# ASD2841.net
KiCad netlist of a schematic drawn in EAGLE
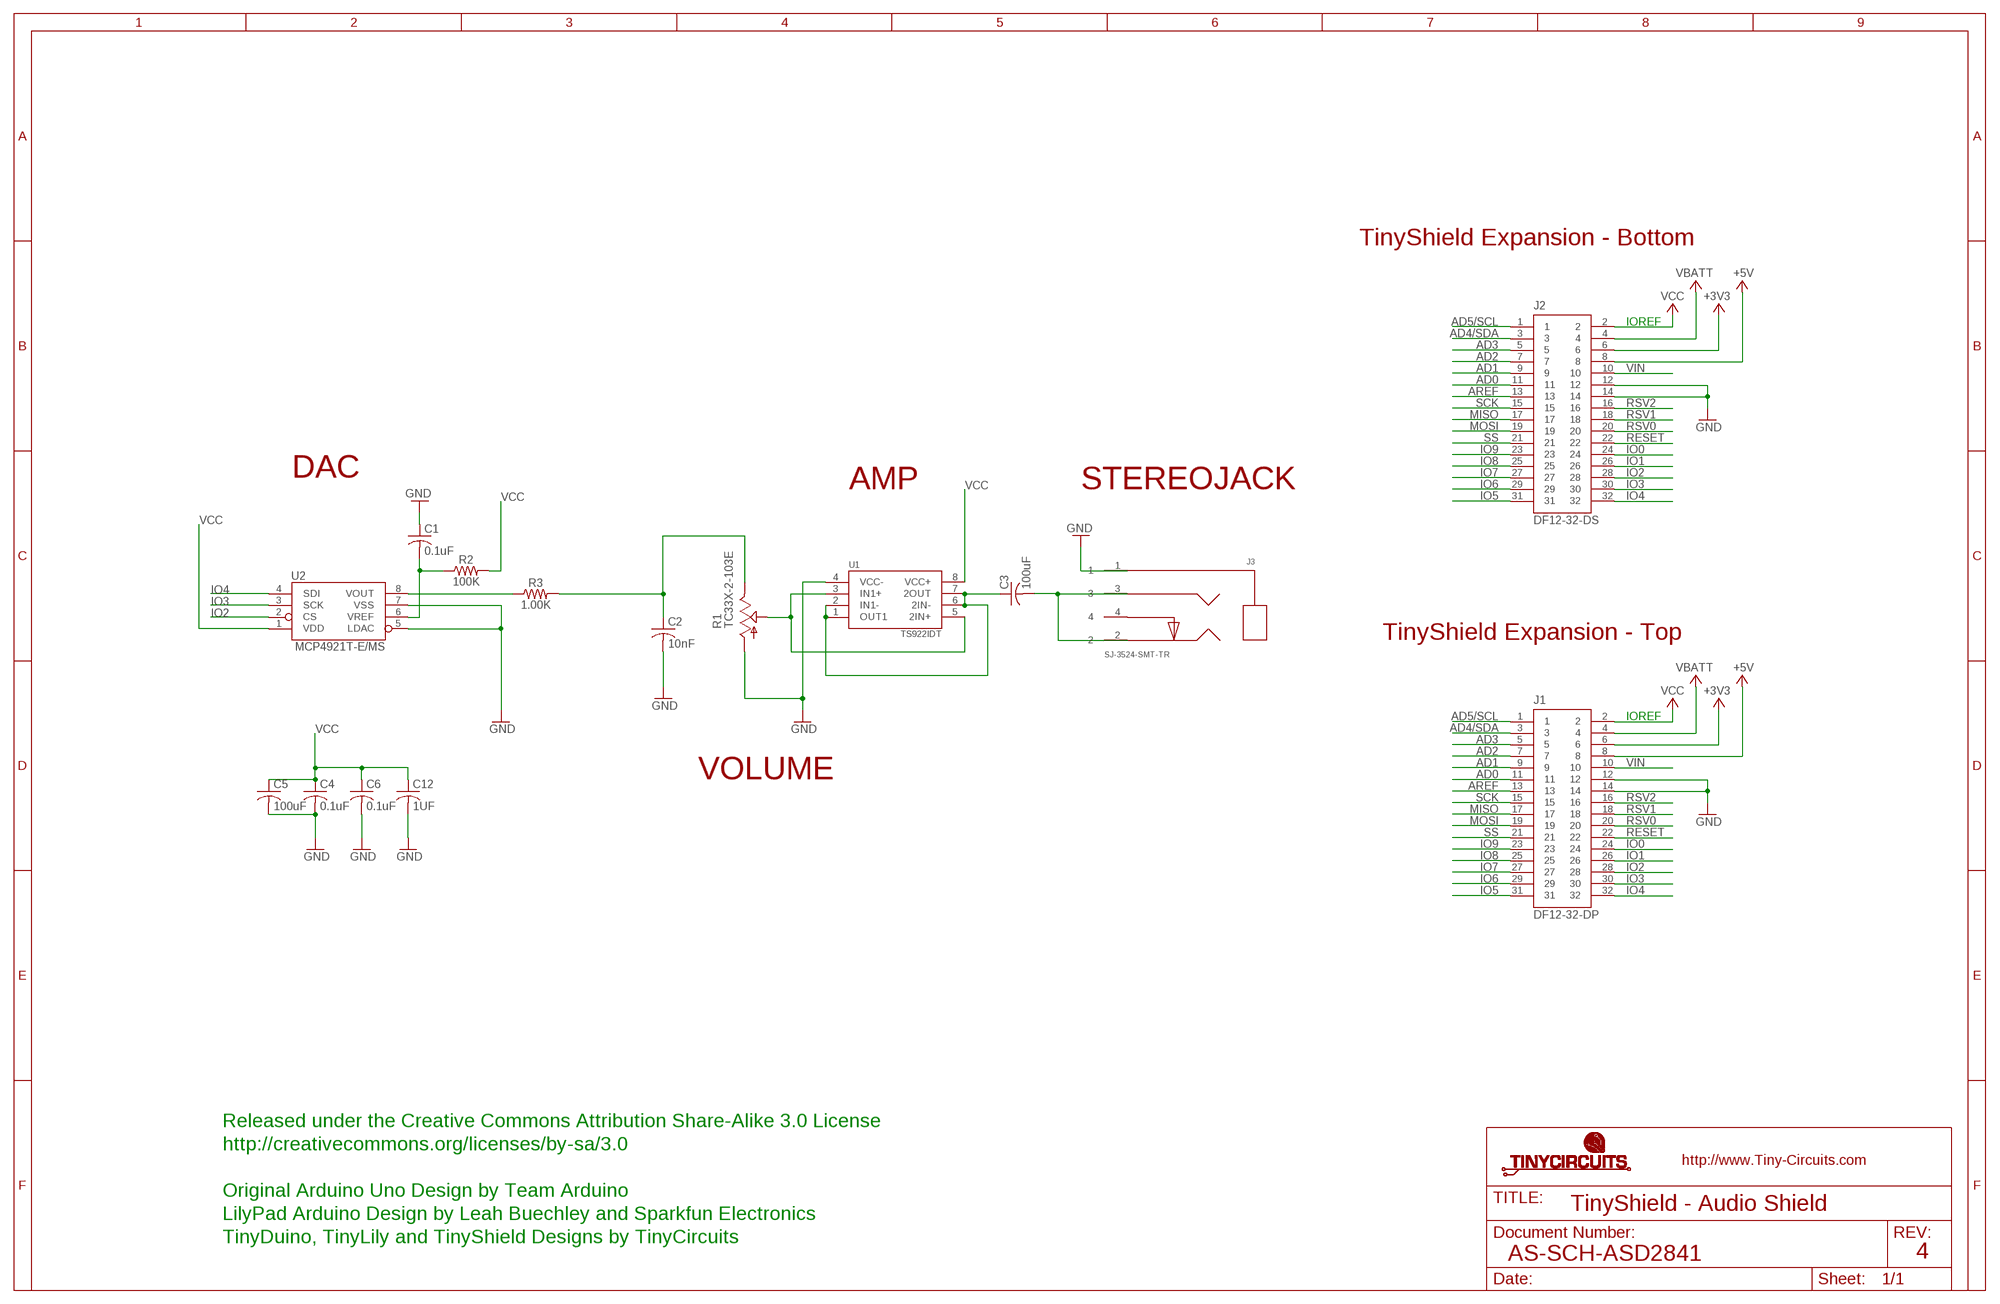
[diagram p0: schematic, sheet 1]

(export (version "E")
  (design (tool "Eeschema 10.0.6"))
  (components
    (comp (ref "C1")
      (value "0.1uF")
      (footprint "eagle-import:C0402")
      (fields (field (name "PARTNO") "AS-ITM-00008"))
      (libsource (lib "eagle-import") (part "AS-ITM-00008"))
    )
    (comp (ref "C2")
      (value "10nF")
      (footprint "eagle-import:C0402")
      (fields (field (name "PARTNO") "AS-ITM-00084"))
      (libsource (lib "eagle-import") (part "AS-ITM-00084"))
    )
    (comp (ref "C3")
      (value "100uF")
      (footprint "eagle-import:C1206")
      (fields (field (name "PARTNO") "AS-ITM-00095"))
      (libsource (lib "eagle-import") (part "AS-ITM-00095"))
    )
    (comp (ref "C4")
      (value "0.1uF")
      (footprint "eagle-import:C0402")
      (fields (field (name "PARTNO") "AS-ITM-00008"))
      (libsource (lib "eagle-import") (part "AS-ITM-00008"))
    )
    (comp (ref "C5")
      (value "100uF")
      (footprint "eagle-import:C1206")
      (fields (field (name "PARTNO") "AS-ITM-00095"))
      (libsource (lib "eagle-import") (part "AS-ITM-00095"))
    )
    (comp (ref "C6")
      (value "0.1uF")
      (footprint "eagle-import:C0402")
      (fields (field (name "PARTNO") "AS-ITM-00008") (field (name "PARTNO_1") "AS-ITM-00008"))
      (libsource (lib "eagle-import") (part "AS-ITM-00008"))
    )
    (comp (ref "C12")
      (value "1UF")
      (footprint "eagle-import:C0402")
      (fields (field (name "PARTNO") "AS-ITM-00105") (field (name "PARTNO_1") "AS-ITM-00105"))
      (libsource (lib "eagle-import") (part "AS-ITM-00105"))
    )
    (comp (ref "J1")
      (value "DF12-32-DP")
      (footprint "eagle-import:DF12-32-DP")
      (fields (field (name "PARTNO") "AS-ITM-00015") (field (name "PARTNO_1") "AS-ITM-00015"))
      (libsource (lib "eagle-import") (part "AS-ITM-00015"))
    )
    (comp (ref "J2")
      (value "DF12-32-DS")
      (footprint "eagle-import:DF12-32-DS")
      (fields (field (name "PARTNO") "AS-ITM-00012") (field (name "PARTNO_1") "AS-ITM-00012"))
      (libsource (lib "eagle-import") (part "AS-ITM-00012"))
    )
    (comp (ref "J3")
      (value "SJ-3524-SMT-TR")
      (footprint "eagle-import:SJ-3524-SMT-TR")
      (fields (field (name "PARTNO") "AS-ITM-00094"))
      (libsource (lib "eagle-import") (part "AS-ITM-00094"))
    )
    (comp (ref "R1")
      (value "TC33X-2-103E")
      (footprint "eagle-import:TC33X-2-104E")
      (fields (field (name "PARTNO") "AS-ITM-00187"))
      (libsource (lib "eagle-import") (part "AS-ITM-00187"))
    )
    (comp (ref "R2")
      (value "100K")
      (footprint "eagle-import:0402")
      (fields (field (name "PARTNO") "AS-ITM-00004"))
      (libsource (lib "eagle-import") (part "AS-ITM-00004"))
    )
    (comp (ref "R3")
      (value "1.00K")
      (footprint "eagle-import:0402")
      (fields (field (name "PARTNO") "AS-ITM-00003"))
      (libsource (lib "eagle-import") (part "AS-ITM-00003"))
    )
    (comp (ref "U1")
      (value "TS922IDT")
      (footprint "eagle-import:SO-08")
      (fields (field (name "PARTNO") "AS-ITM-00092"))
      (libsource (lib "eagle-import") (part "AS-ITM-00092"))
    )
    (comp (ref "U2")
      (value "MCP4921T-E/MS")
      (footprint "eagle-import:MSOP8")
      (fields (field (name "PARTNO") "AS-ITM-00091"))
      (libsource (lib "eagle-import") (part "AS-ITM-00091"))
    )
  )
  (nets
    (net (code "1") (name "+3V3") (class "Default")
      (node (ref "J1") (pin "6") (pinfunction "6_6") (pintype "bidirectional"))
      (node (ref "J2") (pin "6") (pinfunction "6_6") (pintype "bidirectional"))
    )
    (net (code "2") (name "+5V") (class "Default")
      (node (ref "J1") (pin "8") (pinfunction "8_8") (pintype "bidirectional"))
      (node (ref "J2") (pin "8") (pinfunction "8_8") (pintype "bidirectional"))
    )
    (net (code "3") (name "/AD0") (class "Default")
      (node (ref "J1") (pin "11") (pinfunction "11_11") (pintype "bidirectional"))
      (node (ref "J2") (pin "11") (pinfunction "11_11") (pintype "bidirectional"))
    )
    (net (code "4") (name "/AD1") (class "Default")
      (node (ref "J1") (pin "9") (pinfunction "9_9") (pintype "bidirectional"))
      (node (ref "J2") (pin "9") (pinfunction "9_9") (pintype "bidirectional"))
    )
    (net (code "5") (name "/AD2") (class "Default")
      (node (ref "J1") (pin "7") (pinfunction "7_7") (pintype "bidirectional"))
      (node (ref "J2") (pin "7") (pinfunction "7_7") (pintype "bidirectional"))
    )
    (net (code "6") (name "/AD3") (class "Default")
      (node (ref "J1") (pin "5") (pinfunction "5_5") (pintype "bidirectional"))
      (node (ref "J2") (pin "5") (pinfunction "5_5") (pintype "bidirectional"))
    )
    (net (code "7") (name "/AD4{slash}SDA") (class "Default")
      (node (ref "J1") (pin "3") (pinfunction "3_3") (pintype "bidirectional"))
      (node (ref "J2") (pin "3") (pinfunction "3_3") (pintype "bidirectional"))
    )
    (net (code "8") (name "/AD5{slash}SCL") (class "Default")
      (node (ref "J1") (pin "1") (pinfunction "1_1") (pintype "bidirectional"))
      (node (ref "J2") (pin "1") (pinfunction "1_1") (pintype "bidirectional"))
    )
    (net (code "9") (name "/AREF") (class "Default")
      (node (ref "J1") (pin "13") (pinfunction "13_13") (pintype "bidirectional"))
      (node (ref "J2") (pin "13") (pinfunction "13_13") (pintype "bidirectional"))
    )
    (net (code "10") (name "/IO0") (class "Default")
      (node (ref "J1") (pin "24") (pinfunction "24_24") (pintype "bidirectional"))
      (node (ref "J2") (pin "24") (pinfunction "24_24") (pintype "bidirectional"))
    )
    (net (code "11") (name "/IO1") (class "Default")
      (node (ref "J1") (pin "26") (pinfunction "26_26") (pintype "bidirectional"))
      (node (ref "J2") (pin "26") (pinfunction "26_26") (pintype "bidirectional"))
    )
    (net (code "12") (name "/IO2") (class "Default")
      (node (ref "J1") (pin "28") (pinfunction "28_28") (pintype "bidirectional"))
      (node (ref "J2") (pin "28") (pinfunction "28_28") (pintype "bidirectional"))
      (node (ref "U2") (pin "2") (pinfunction "CS_2") (pintype "bidirectional"))
    )
    (net (code "13") (name "/IO3") (class "Default")
      (node (ref "J1") (pin "30") (pinfunction "30_30") (pintype "bidirectional"))
      (node (ref "J2") (pin "30") (pinfunction "30_30") (pintype "bidirectional"))
      (node (ref "U2") (pin "3") (pinfunction "SCK_3") (pintype "bidirectional"))
    )
    (net (code "14") (name "/IO4") (class "Default")
      (node (ref "J1") (pin "32") (pinfunction "32_32") (pintype "bidirectional"))
      (node (ref "J2") (pin "32") (pinfunction "32_32") (pintype "bidirectional"))
      (node (ref "U2") (pin "4") (pinfunction "SDI_4") (pintype "bidirectional"))
    )
    (net (code "15") (name "/IO5") (class "Default")
      (node (ref "J1") (pin "31") (pinfunction "31_31") (pintype "bidirectional"))
      (node (ref "J2") (pin "31") (pinfunction "31_31") (pintype "bidirectional"))
    )
    (net (code "16") (name "/IO6") (class "Default")
      (node (ref "J1") (pin "29") (pinfunction "29_29") (pintype "bidirectional"))
      (node (ref "J2") (pin "29") (pinfunction "29_29") (pintype "bidirectional"))
    )
    (net (code "17") (name "/IO7") (class "Default")
      (node (ref "J1") (pin "27") (pinfunction "27_27") (pintype "bidirectional"))
      (node (ref "J2") (pin "27") (pinfunction "27_27") (pintype "bidirectional"))
    )
    (net (code "18") (name "/IO8") (class "Default")
      (node (ref "J1") (pin "25") (pinfunction "25_25") (pintype "bidirectional"))
      (node (ref "J2") (pin "25") (pinfunction "25_25") (pintype "bidirectional"))
    )
    (net (code "19") (name "/IO9") (class "Default")
      (node (ref "J1") (pin "23") (pinfunction "23_23") (pintype "bidirectional"))
      (node (ref "J2") (pin "23") (pinfunction "23_23") (pintype "bidirectional"))
    )
    (net (code "20") (name "/MISO") (class "Default")
      (node (ref "J1") (pin "17") (pinfunction "17_17") (pintype "bidirectional"))
      (node (ref "J2") (pin "17") (pinfunction "17_17") (pintype "bidirectional"))
    )
    (net (code "21") (name "/MOSI") (class "Default")
      (node (ref "J1") (pin "19") (pinfunction "19_19") (pintype "bidirectional"))
      (node (ref "J2") (pin "19") (pinfunction "19_19") (pintype "bidirectional"))
    )
    (net (code "22") (name "/RESET") (class "Default")
      (node (ref "J1") (pin "22") (pinfunction "22_22") (pintype "bidirectional"))
      (node (ref "J2") (pin "22") (pinfunction "22_22") (pintype "bidirectional"))
    )
    (net (code "23") (name "/RSV0") (class "Default")
      (node (ref "J1") (pin "20") (pinfunction "20_20") (pintype "bidirectional"))
      (node (ref "J2") (pin "20") (pinfunction "20_20") (pintype "bidirectional"))
    )
    (net (code "24") (name "/RSV1") (class "Default")
      (node (ref "J1") (pin "18") (pinfunction "18_18") (pintype "bidirectional"))
      (node (ref "J2") (pin "18") (pinfunction "18_18") (pintype "bidirectional"))
    )
    (net (code "25") (name "/RSV2") (class "Default")
      (node (ref "J1") (pin "16") (pinfunction "16_16") (pintype "bidirectional"))
      (node (ref "J2") (pin "16") (pinfunction "16_16") (pintype "bidirectional"))
    )
    (net (code "26") (name "/SCK") (class "Default")
      (node (ref "J1") (pin "15") (pinfunction "15_15") (pintype "bidirectional"))
      (node (ref "J2") (pin "15") (pinfunction "15_15") (pintype "bidirectional"))
    )
    (net (code "27") (name "/SS") (class "Default")
      (node (ref "J1") (pin "21") (pinfunction "21_21") (pintype "bidirectional"))
      (node (ref "J2") (pin "21") (pinfunction "21_21") (pintype "bidirectional"))
    )
    (net (code "28") (name "/VIN") (class "Default")
      (node (ref "J1") (pin "10") (pinfunction "10_10") (pintype "bidirectional"))
      (node (ref "J2") (pin "10") (pinfunction "10_10") (pintype "bidirectional"))
    )
    (net (code "29") (name "GND") (class "Default")
      (node (ref "C1") (pin "1") (pinfunction "1_1") (pintype "passive"))
      (node (ref "C12") (pin "2") (pinfunction "2_2") (pintype "passive"))
      (node (ref "C2") (pin "2") (pinfunction "2_2") (pintype "passive"))
      (node (ref "C4") (pin "2") (pinfunction "2_2") (pintype "passive"))
      (node (ref "C5") (pin "2") (pinfunction "2_2") (pintype "passive"))
      (node (ref "C6") (pin "2") (pinfunction "2_2") (pintype "passive"))
      (node (ref "J1") (pin "12") (pinfunction "12_12") (pintype "bidirectional"))
      (node (ref "J1") (pin "14") (pinfunction "14_14") (pintype "bidirectional"))
      (node (ref "J2") (pin "12") (pinfunction "12_12") (pintype "bidirectional"))
      (node (ref "J2") (pin "14") (pinfunction "14_14") (pintype "bidirectional"))
      (node (ref "J3") (pin "1") (pinfunction "1_1") (pintype "bidirectional"))
      (node (ref "R1") (pin "1") (pinfunction "A_1") (pintype "passive"))
      (node (ref "U1") (pin "4") (pinfunction "VCC-_4") (pintype "bidirectional"))
      (node (ref "U2") (pin "5") (pinfunction "LDAC_5") (pintype "bidirectional"))
      (node (ref "U2") (pin "7") (pinfunction "VSS_7") (pintype "bidirectional"))
    )
    (net (code "30") (name "Net-(C3-Pad2)") (class "Default")
      (node (ref "C3") (pin "2") (pinfunction "2_2") (pintype "passive"))
      (node (ref "J3") (pin "2") (pinfunction "2_2") (pintype "bidirectional"))
      (node (ref "J3") (pin "3") (pinfunction "3_3") (pintype "bidirectional"))
    )
    (net (code "31") (name "Net-(R1-E)") (class "Default")
      (node (ref "C2") (pin "1") (pinfunction "1_1") (pintype "passive"))
      (node (ref "R1") (pin "3") (pinfunction "E_3") (pintype "passive"))
      (node (ref "R3") (pin "2") (pinfunction "2_2") (pintype "passive"))
    )
    (net (code "32") (name "Net-(R1-S)") (class "Default")
      (node (ref "R1") (pin "2") (pinfunction "S_2") (pintype "passive"))
      (node (ref "U1") (pin "3") (pinfunction "IN1+_3") (pintype "bidirectional"))
      (node (ref "U1") (pin "5") (pinfunction "2IN+_5") (pintype "bidirectional"))
    )
    (net (code "33") (name "Net-(U1-2IN-)") (class "Default")
      (node (ref "C3") (pin "1") (pinfunction "1_1") (pintype "passive"))
      (node (ref "U1") (pin "1") (pinfunction "OUT1_1") (pintype "bidirectional"))
      (node (ref "U1") (pin "2") (pinfunction "IN1-_2") (pintype "bidirectional"))
      (node (ref "U1") (pin "6") (pinfunction "2IN-_6") (pintype "bidirectional"))
      (node (ref "U1") (pin "7") (pinfunction "2OUT_7") (pintype "bidirectional"))
    )
    (net (code "34") (name "Net-(U2-VOUT)") (class "Default")
      (node (ref "R3") (pin "1") (pinfunction "1_1") (pintype "passive"))
      (node (ref "U2") (pin "8") (pinfunction "VOUT_8") (pintype "bidirectional"))
    )
    (net (code "35") (name "Net-(U2-VREF)") (class "Default")
      (node (ref "C1") (pin "2") (pinfunction "2_2") (pintype "passive"))
      (node (ref "R2") (pin "1") (pinfunction "1_1") (pintype "passive"))
      (node (ref "U2") (pin "6") (pinfunction "VREF_6") (pintype "bidirectional"))
    )
    (net (code "36") (name "VBATT") (class "Default")
      (node (ref "J1") (pin "4") (pinfunction "4_4") (pintype "bidirectional"))
      (node (ref "J2") (pin "4") (pinfunction "4_4") (pintype "bidirectional"))
    )
    (net (code "37") (name "VCC") (class "Default")
      (node (ref "C12") (pin "1") (pinfunction "1_1") (pintype "passive"))
      (node (ref "C4") (pin "1") (pinfunction "1_1") (pintype "passive"))
      (node (ref "C5") (pin "1") (pinfunction "1_1") (pintype "passive"))
      (node (ref "C6") (pin "1") (pinfunction "1_1") (pintype "passive"))
      (node (ref "J1") (pin "2") (pinfunction "2_2") (pintype "bidirectional"))
      (node (ref "J2") (pin "2") (pinfunction "2_2") (pintype "bidirectional"))
      (node (ref "R2") (pin "2") (pinfunction "2_2") (pintype "passive"))
      (node (ref "U1") (pin "8") (pinfunction "VCC+_8") (pintype "bidirectional"))
      (node (ref "U2") (pin "1") (pinfunction "VDD_1") (pintype "bidirectional"))
    )
    (net (code "38") (name "unconnected-(J3-Pad4)") (class "Default")
      (node (ref "J3") (pin "4") (pinfunction "4_4") (pintype "bidirectional"))
    )
  )
)
